# SNC8600.net
KiCad netlist of a schematic drawn in Altium Designer
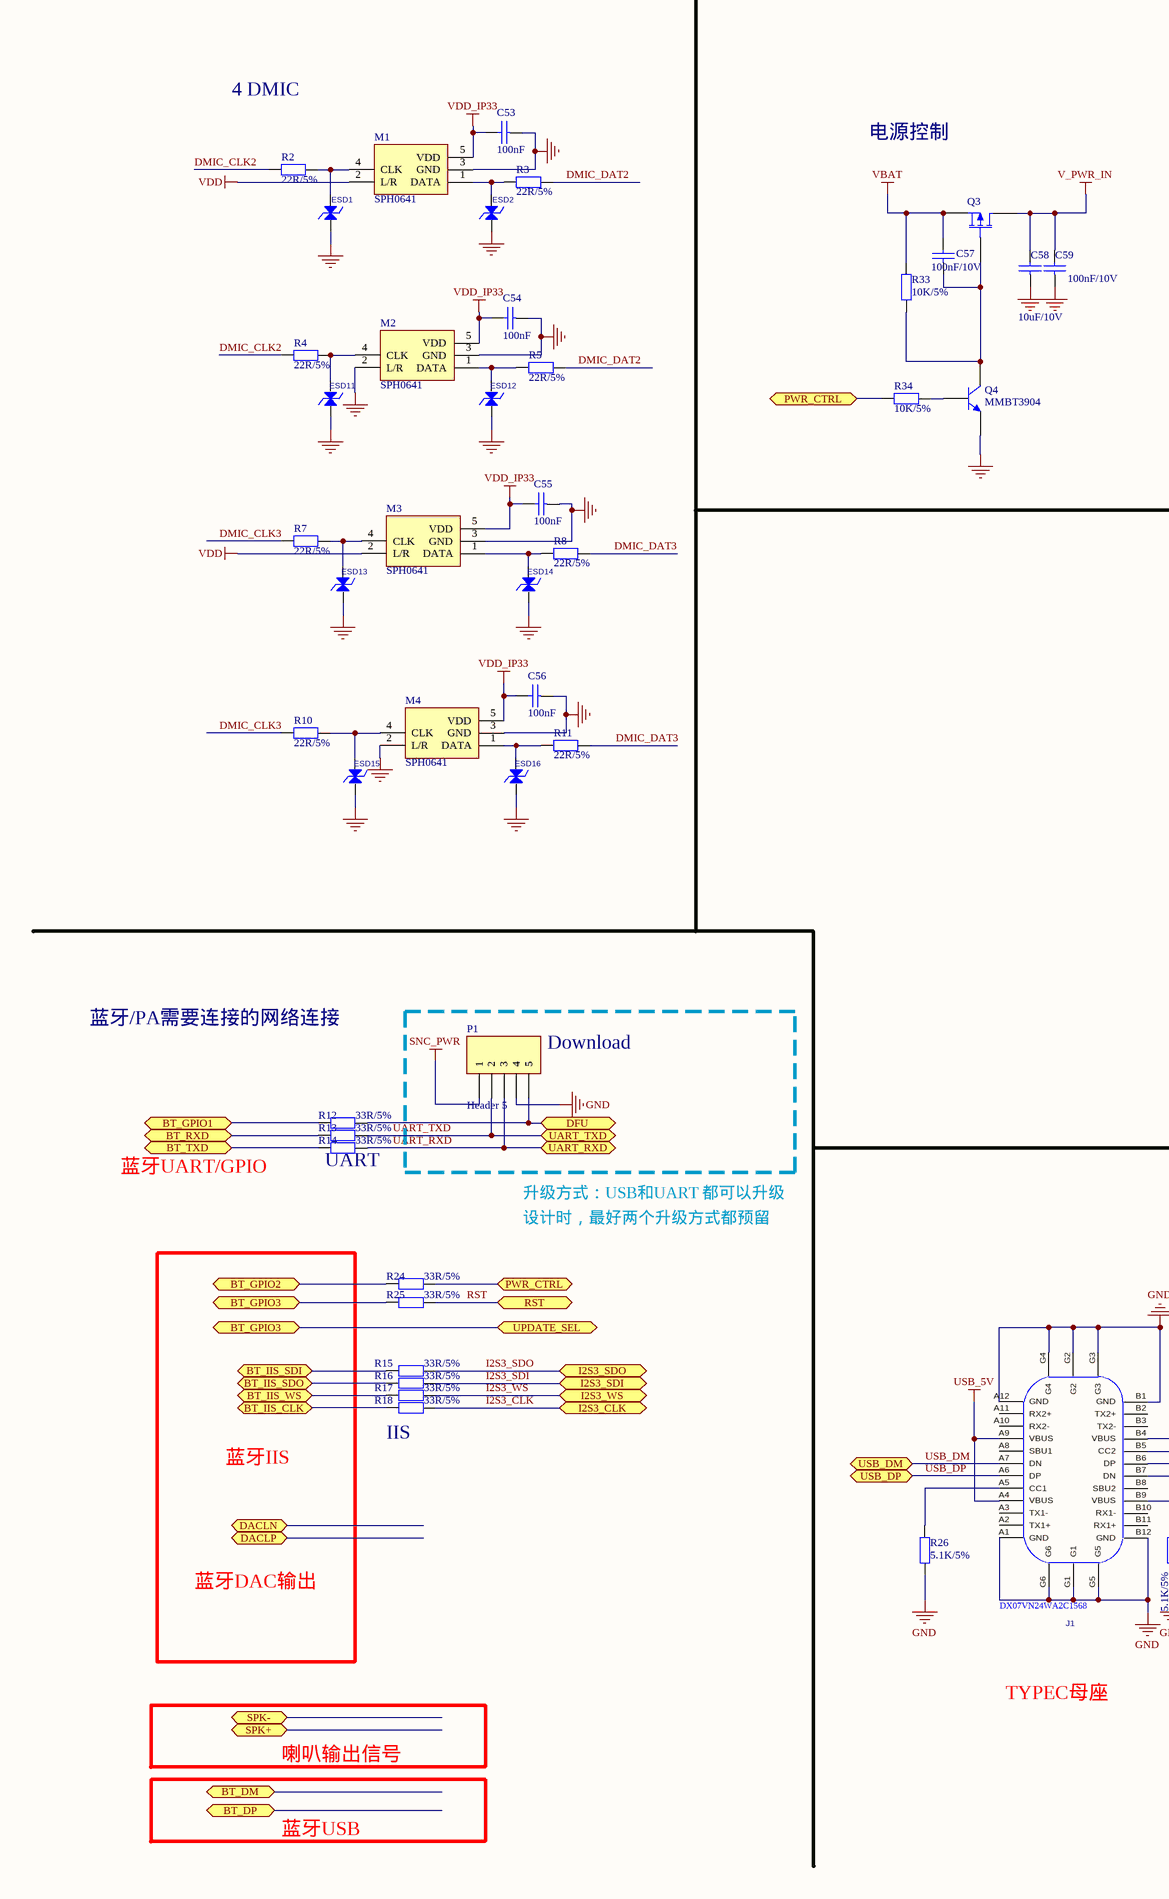
[diagram p0: SNC8600.SchDoc, left]
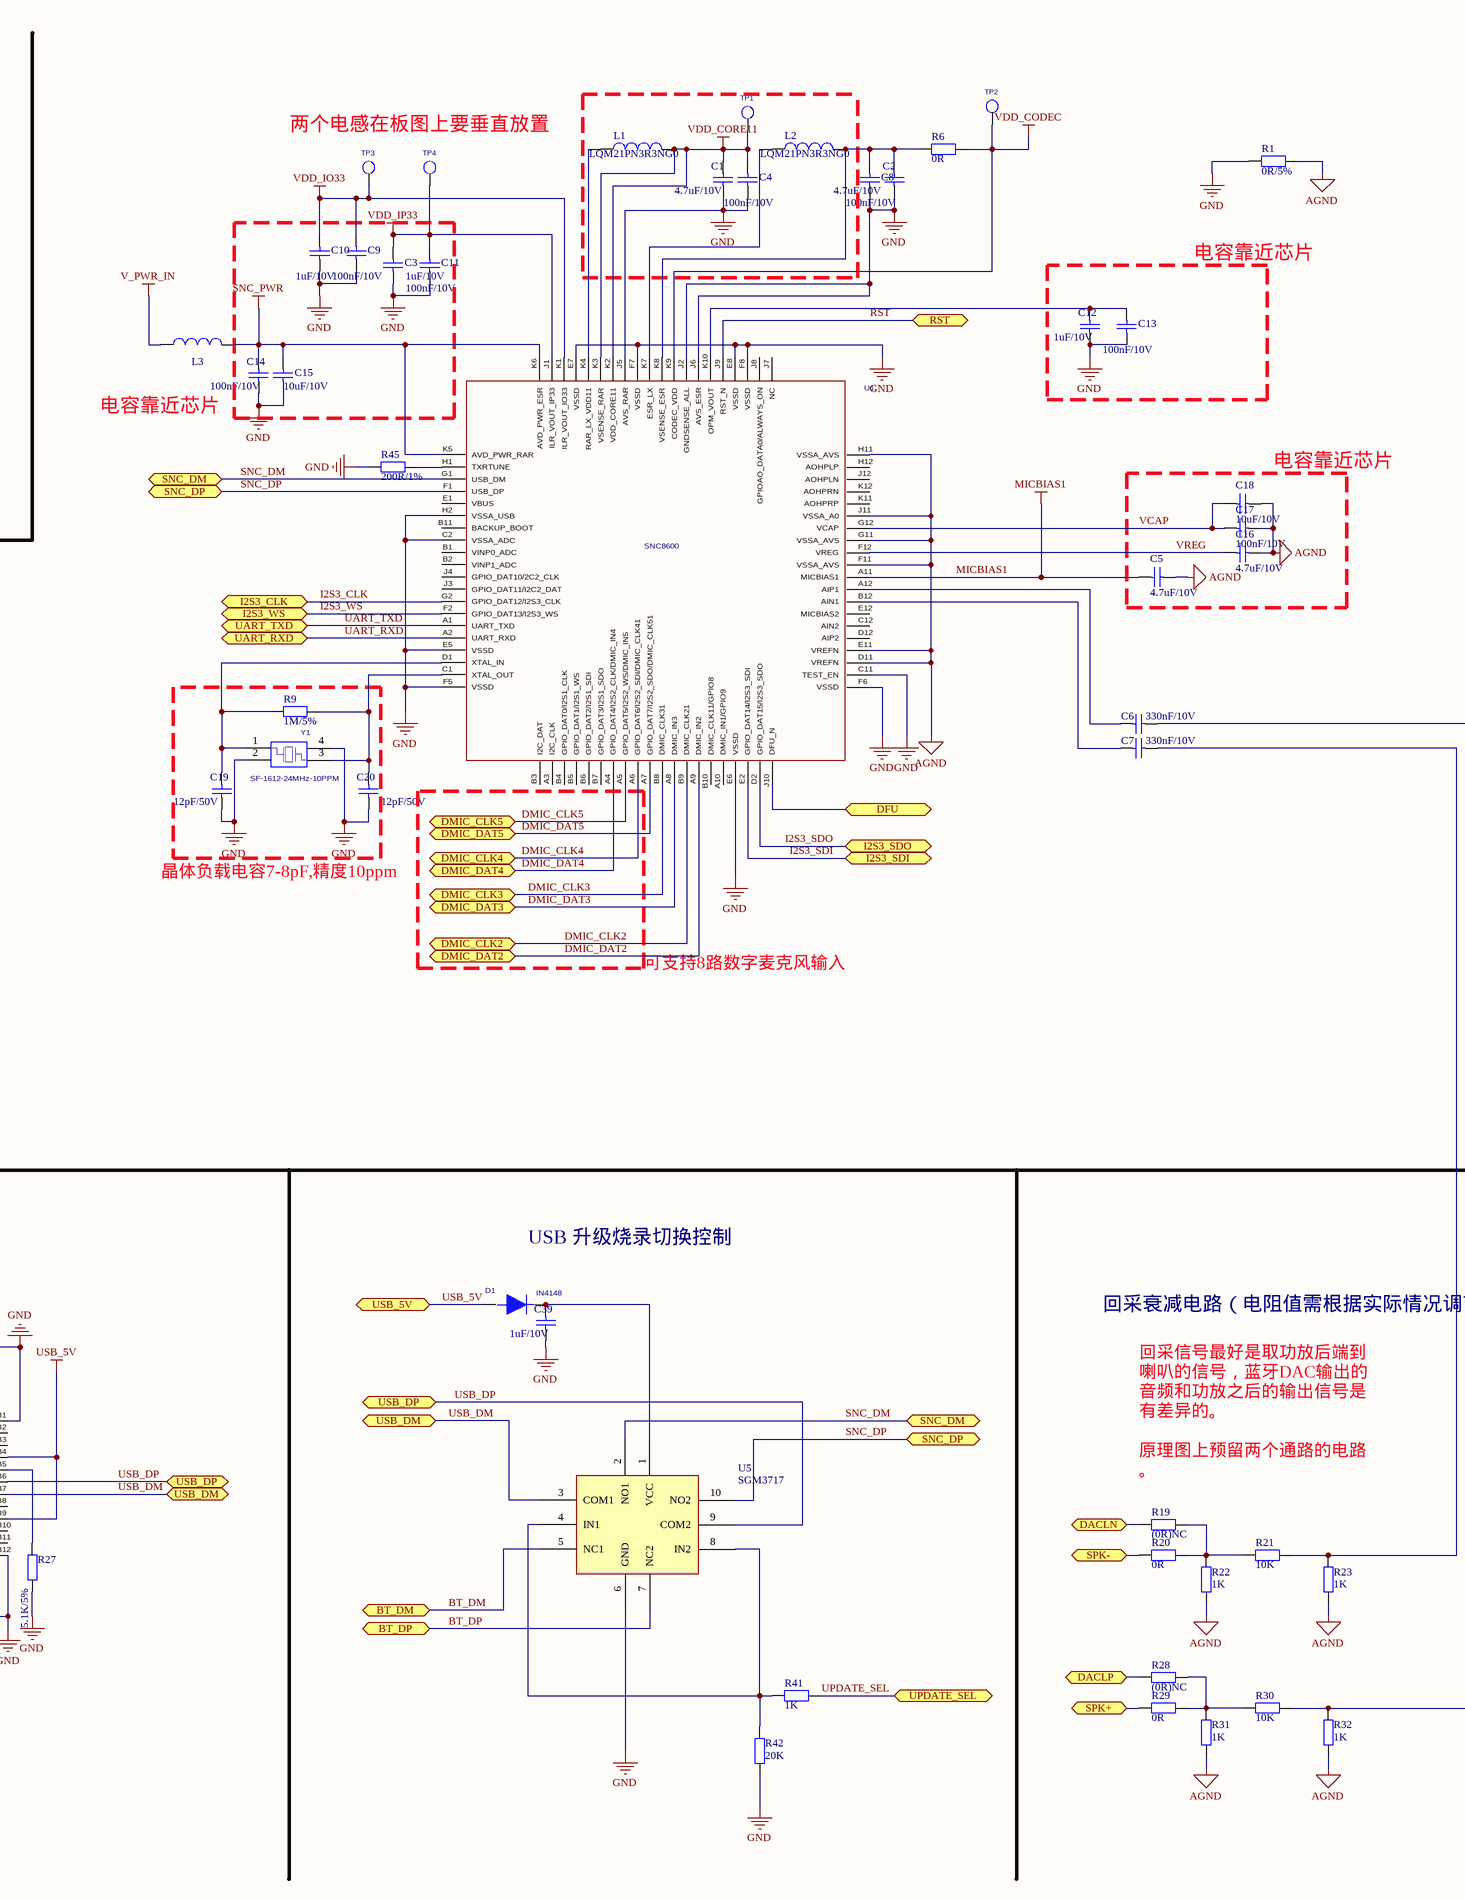
[diagram p1: SNC8600.SchDoc, right]

(export (version "E")
  (design (tool "Eeschema 10.0.6"))
  (components
    (comp (ref "C1")
      (value "4.7uF/10V")
      (footprint "C0603")
      (description "Capacitor (Semiconductor SIM Model)")
      (fields (field (name "PUBLISHER") "Altium Limited"))
      (libsource (lib "Miscellaneous Devices") (part "Cap Semi"))
    )
    (comp (ref "C2")
      (value "4.7uF/10V")
      (footprint "C0603")
      (description "Capacitor (Semiconductor SIM Model)")
      (fields (field (name "PUBLISHER") "Altium Limited"))
      (libsource (lib "Miscellaneous Devices") (part "Cap Semi"))
    )
    (comp (ref "C3")
      (value "1uF/10V")
      (footprint "C0603")
      (description "Capacitor (Semiconductor SIM Model)")
      (fields (field (name "PUBLISHER") "Altium Limited"))
      (libsource (lib "Miscellaneous Devices") (part "Cap Semi"))
    )
    (comp (ref "C4")
      (value "100nF/10V")
      (footprint "C0603")
      (description "Capacitor (Semiconductor SIM Model)")
      (fields (field (name "PUBLISHER") "Altium Limited"))
      (libsource (lib "Miscellaneous Devices") (part "Cap Semi"))
    )
    (comp (ref "C5")
      (value "4.7uF/10V")
      (footprint "C0603")
      (description "Capacitor (Semiconductor SIM Model)")
      (fields (field (name "PUBLISHER") "Altium Limited"))
      (libsource (lib "Miscellaneous Devices") (part "Cap Semi"))
    )
    (comp (ref "C6")
      (value "330nF/10V")
      (footprint "C0603")
      (description "Capacitor (Semiconductor SIM Model)")
      (fields (field (name "PUBLISHER") "Altium Limited"))
      (libsource (lib "Miscellaneous Devices") (part "Cap Semi"))
    )
    (comp (ref "C7")
      (value "330nF/10V")
      (footprint "C0603")
      (description "Capacitor (Semiconductor SIM Model)")
      (fields (field (name "PUBLISHER") "Altium Limited"))
      (libsource (lib "Miscellaneous Devices") (part "Cap Semi"))
    )
    (comp (ref "C8")
      (value "100nF/10V")
      (footprint "C0603")
      (description "Capacitor (Semiconductor SIM Model)")
      (fields (field (name "PUBLISHER") "Altium Limited"))
      (libsource (lib "Miscellaneous Devices") (part "Cap Semi"))
    )
    (comp (ref "C9")
      (value "100nF/10V")
      (footprint "C0603")
      (description "Capacitor (Semiconductor SIM Model)")
      (fields (field (name "PUBLISHER") "Altium Limited"))
      (libsource (lib "Miscellaneous Devices") (part "Cap Semi"))
    )
    (comp (ref "C10")
      (value "1uF/10V")
      (footprint "C0603")
      (description "Capacitor (Semiconductor SIM Model)")
      (fields (field (name "PUBLISHER") "Altium Limited"))
      (libsource (lib "Miscellaneous Devices") (part "Cap Semi"))
    )
    (comp (ref "C11")
      (value "100nF/10V")
      (footprint "C0603")
      (description "Capacitor (Semiconductor SIM Model)")
      (fields (field (name "PUBLISHER") "Altium Limited"))
      (libsource (lib "Miscellaneous Devices") (part "Cap Semi"))
    )
    (comp (ref "C12")
      (value "1uF/10V")
      (footprint "C0603")
      (description "Capacitor (Semiconductor SIM Model)")
      (fields (field (name "PUBLISHER") "Altium Limited"))
      (libsource (lib "Miscellaneous Devices") (part "Cap Semi"))
    )
    (comp (ref "C13")
      (value "100nF/10V")
      (footprint "C0603")
      (description "Capacitor (Semiconductor SIM Model)")
      (fields (field (name "PUBLISHER") "Altium Limited"))
      (libsource (lib "Miscellaneous Devices") (part "Cap Semi"))
    )
    (comp (ref "C14")
      (value "100nF/10V")
      (footprint "C0603")
      (description "Capacitor (Semiconductor SIM Model)")
      (fields (field (name "PUBLISHER") "Altium Limited"))
      (libsource (lib "Miscellaneous Devices") (part "Cap Semi"))
    )
    (comp (ref "C15")
      (value "10uF/10V")
      (footprint "C0603")
      (description "Capacitor (Semiconductor SIM Model)")
      (fields (field (name "PUBLISHER") "Altium Limited"))
      (libsource (lib "Miscellaneous Devices") (part "Cap Semi"))
    )
    (comp (ref "C16")
      (value "4.7uF/10V")
      (footprint "C0603")
      (description "Capacitor (Semiconductor SIM Model)")
      (fields (field (name "PUBLISHER") "Altium Limited"))
      (libsource (lib "Miscellaneous Devices") (part "Cap Semi"))
    )
    (comp (ref "C17")
      (value "100nF/10V")
      (footprint "C0603")
      (description "Capacitor (Semiconductor SIM Model)")
      (fields (field (name "PUBLISHER") "Altium Limited"))
      (libsource (lib "Miscellaneous Devices") (part "Cap Semi"))
    )
    (comp (ref "C18")
      (value "10uF/10V")
      (footprint "C0603")
      (description "Capacitor (Semiconductor SIM Model)")
      (fields (field (name "PUBLISHER") "Altium Limited"))
      (libsource (lib "Miscellaneous Devices") (part "Cap Semi"))
    )
    (comp (ref "C19")
      (value "12pF/50V")
      (footprint "C0603")
      (description "Capacitor (Semiconductor SIM Model)")
      (fields (field (name "PUBLISHER") "Altium Limited"))
      (libsource (lib "Miscellaneous Devices") (part "Cap Semi"))
    )
    (comp (ref "C20")
      (value "12pF/50V")
      (footprint "C0603")
      (description "Capacitor (Semiconductor SIM Model)")
      (fields (field (name "PUBLISHER") "Altium Limited"))
      (libsource (lib "Miscellaneous Devices") (part "Cap Semi"))
    )
    (comp (ref "C39")
      (value "1uF/10V")
      (footprint "C0603")
      (description "Capacitor (Semiconductor SIM Model)")
      (fields (field (name "PUBLISHER") "Altium Limited"))
      (libsource (lib "Miscellaneous Devices") (part "Cap Semi"))
    )
    (comp (ref "C53")
      (value "100nF")
      (footprint "0201")
      (description "Capacitor")
      (libsource (lib "MIC1") (part "CAP-0201"))
    )
    (comp (ref "C54")
      (value "100nF")
      (footprint "0201")
      (description "Capacitor")
      (libsource (lib "MIC1") (part "CAP-0201"))
    )
    (comp (ref "C55")
      (value "100nF")
      (footprint "0201")
      (description "Capacitor")
      (libsource (lib "MIC1") (part "CAP-0201"))
    )
    (comp (ref "C56")
      (value "100nF")
      (footprint "0201")
      (description "Capacitor")
      (libsource (lib "MIC1") (part "CAP-0201"))
    )
    (comp (ref "C57")
      (value "100nF/10V")
      (footprint "0201")
      (description "Capacitor")
      (libsource (lib "*") (part "CAP"))
    )
    (comp (ref "C58")
      (value "10uF/10V")
      (footprint "C0402")
      (description "Capacitor")
      (libsource (lib "电容") (part "普通电容"))
    )
    (comp (ref "C59")
      (value "100nF/10V")
      (footprint "0201")
      (description "Capacitor")
      (libsource (lib "电容") (part "普通电容"))
    )
    (comp (ref "D1")
      (value "IN4148")
      (footprint "SMD")
      (fields (field (name "Comment") "D-IN4148-SMT"))
      (libsource (lib "*") (part "D-IN4148-SMT"))
    )
    (comp (ref "ESD1")
      (value "~")
      (footprint "0402 DFN")
      (libsource (lib "EVB-SCH-LCD-202003152") (part "ESD"))
    )
    (comp (ref "ESD2")
      (value "~")
      (footprint "0402 DFN")
      (libsource (lib "EVB-SCH-LCD-202003152") (part "ESD"))
    )
    (comp (ref "ESD11")
      (value "~")
      (footprint "0402 DFN")
      (libsource (lib "EVB-SCH-LCD-202003152") (part "ESD"))
    )
    (comp (ref "ESD12")
      (value "~")
      (footprint "0402 DFN")
      (libsource (lib "EVB-SCH-LCD-202003152") (part "ESD"))
    )
    (comp (ref "ESD13")
      (value "~")
      (footprint "0402 DFN")
      (libsource (lib "EVB-SCH-LCD-202003152") (part "ESD"))
    )
    (comp (ref "ESD14")
      (value "~")
      (footprint "0402 DFN")
      (libsource (lib "EVB-SCH-LCD-202003152") (part "ESD"))
    )
    (comp (ref "ESD15")
      (value "~")
      (footprint "0402 DFN")
      (libsource (lib "EVB-SCH-LCD-202003152") (part "ESD"))
    )
    (comp (ref "ESD16")
      (value "~")
      (footprint "0402 DFN")
      (libsource (lib "EVB-SCH-LCD-202003152") (part "ESD"))
    )
    (comp (ref "J1")
      (value "TYPEC")
      (footprint "USB-TYPEC")
      (libsource (lib "EVB-SCH-LCD-202003152") (part "TYPEC"))
    )
    (comp (ref "L1")
      (value "LQM21PN3R3NG0")
      (footprint "L0805")
      (description "Inductor")
      (fields (field (name "PUBLISHER") "Altium Limited"))
      (libsource (lib "Miscellaneous Devices") (part "Inductor"))
    )
    (comp (ref "L2")
      (value "LQM21PN3R3NG0")
      (footprint "L0805")
      (description "Inductor")
      (fields (field (name "PUBLISHER") "Altium Limited"))
      (libsource (lib "Miscellaneous Devices") (part "Inductor"))
    )
    (comp (ref "L3")
      (value "~")
      (footprint "R0402")
      (description "Inductor")
      (fields (field (name "PUBLISHER") "Altium Limited"))
      (libsource (lib "Miscellaneous Devices") (part "Inductor"))
    )
    (comp (ref "M1")
      (value "SPH0641")
      (footprint "SPH_3526")
      (description "MEMS MICPHONE")
      (fields (field (name "PUBLISHER") "Altium Limited"))
      (libsource (lib "MIC1") (part "SPH0641"))
    )
    (comp (ref "M2")
      (value "SPH0641")
      (footprint "SPH_3526")
      (description "MEMS MICPHONE")
      (fields (field (name "PUBLISHER") "Altium Limited"))
      (libsource (lib "MIC1") (part "SPH0641"))
    )
    (comp (ref "M3")
      (value "SPH0641")
      (footprint "SPH_3526")
      (description "MEMS MICPHONE")
      (fields (field (name "PUBLISHER") "Altium Limited"))
      (libsource (lib "MIC1") (part "SPH0641"))
    )
    (comp (ref "M4")
      (value "SPH0641")
      (footprint "SPH_3526")
      (description "MEMS MICPHONE")
      (fields (field (name "PUBLISHER") "Altium Limited"))
      (libsource (lib "MIC1") (part "SPH0641"))
    )
    (comp (ref "P1")
      (value "Header 5")
      (footprint "HDR1X5")
      (description "Header, 5-Pin")
      (fields (field (name "PUBLISHER") "Altium Limited"))
      (libsource (lib "Miscellaneous Connectors") (part "Header 5"))
    )
    (comp (ref "Q3")
      (value "~")
      (footprint "SOT23_3407")
      (description "P-Channel MOSFET")
      (fields (field (name "PUBLISHER") "Altium Limited"))
      (libsource (lib "Miscellaneous Devices") (part "MOSFET-P"))
    )
    (comp (ref "Q4")
      (value "MMBT3904")
      (footprint "SOT23")
      (description "NPN General Purpose Amplifier")
      (fields (field (name "PUBLISHER") "Altium Limited"))
      (libsource (lib "Miscellaneous Devices") (part "2N3904"))
    )
    (comp (ref "R1")
      (value "0R/5%")
      (footprint "R0603")
      (description "Resistor")
      (fields (field (name "PUBLISHER") "Altium Limited"))
      (libsource (lib "") (part "Res2_1"))
    )
    (comp (ref "R2")
      (value "22R/5%")
      (footprint "0201")
      (description "Resistor")
      (fields (field (name "PUBLISHER") "Altium Limited"))
      (libsource (lib "Miscellaneous Devices") (part "Res2"))
    )
    (comp (ref "R3")
      (value "22R/5%")
      (footprint "0201")
      (description "Resistor")
      (fields (field (name "PUBLISHER") "Altium Limited"))
      (libsource (lib "Miscellaneous Devices") (part "Res2"))
    )
    (comp (ref "R4")
      (value "22R/5%")
      (footprint "0201")
      (description "Resistor")
      (fields (field (name "PUBLISHER") "Altium Limited"))
      (libsource (lib "Miscellaneous Devices") (part "Res2"))
    )
    (comp (ref "R5")
      (value "22R/5%")
      (footprint "0201")
      (description "Resistor")
      (fields (field (name "PUBLISHER") "Altium Limited"))
      (libsource (lib "Miscellaneous Devices") (part "Res2"))
    )
    (comp (ref "R6")
      (value "0R")
      (footprint "R0603")
      (description "Resistor")
      (fields (field (name "PUBLISHER") "Altium Limited"))
      (libsource (lib "") (part "Res2_1"))
    )
    (comp (ref "R7")
      (value "22R/5%")
      (footprint "0201")
      (description "Resistor")
      (fields (field (name "PUBLISHER") "Altium Limited"))
      (libsource (lib "Miscellaneous Devices") (part "Res2"))
    )
    (comp (ref "R8")
      (value "22R/5%")
      (footprint "0201")
      (description "Resistor")
      (fields (field (name "PUBLISHER") "Altium Limited"))
      (libsource (lib "Miscellaneous Devices") (part "Res2"))
    )
    (comp (ref "R9")
      (value "1M/5%")
      (footprint "R0603")
      (description "Resistor")
      (fields (field (name "PUBLISHER") "Altium Limited"))
      (libsource (lib "") (part "Res2_1"))
    )
    (comp (ref "R10")
      (value "22R/5%")
      (footprint "0201")
      (description "Resistor")
      (fields (field (name "PUBLISHER") "Altium Limited"))
      (libsource (lib "Miscellaneous Devices") (part "Res2"))
    )
    (comp (ref "R11")
      (value "22R/5%")
      (footprint "0201")
      (description "Resistor")
      (fields (field (name "PUBLISHER") "Altium Limited"))
      (libsource (lib "Miscellaneous Devices") (part "Res2"))
    )
    (comp (ref "R12")
      (value "33R/5%")
      (footprint "R0603")
      (description "Resistor")
      (fields (field (name "PUBLISHER") "Altium Limited"))
      (libsource (lib "Miscellaneous Devices") (part "Res2"))
    )
    (comp (ref "R13")
      (value "33R/5%")
      (footprint "R0603")
      (description "Resistor")
      (fields (field (name "PUBLISHER") "Altium Limited"))
      (libsource (lib "Miscellaneous Devices") (part "Res2"))
    )
    (comp (ref "R14")
      (value "33R/5%")
      (footprint "R0603")
      (description "Resistor")
      (fields (field (name "PUBLISHER") "Altium Limited"))
      (libsource (lib "Miscellaneous Devices") (part "Res2"))
    )
    (comp (ref "R15")
      (value "33R/5%")
      (footprint "R0603")
      (description "Resistor")
      (fields (field (name "PUBLISHER") "Altium Limited"))
      (libsource (lib "Miscellaneous Devices") (part "Res2"))
    )
    (comp (ref "R16")
      (value "33R/5%")
      (footprint "R0603")
      (description "Resistor")
      (fields (field (name "PUBLISHER") "Altium Limited"))
      (libsource (lib "Miscellaneous Devices") (part "Res2"))
    )
    (comp (ref "R17")
      (value "33R/5%")
      (footprint "R0603")
      (description "Resistor")
      (fields (field (name "PUBLISHER") "Altium Limited"))
      (libsource (lib "Miscellaneous Devices") (part "Res2"))
    )
    (comp (ref "R18")
      (value "33R/5%")
      (footprint "R0603")
      (description "Resistor")
      (fields (field (name "PUBLISHER") "Altium Limited"))
      (libsource (lib "Miscellaneous Devices") (part "Res2"))
    )
    (comp (ref "R19")
      (value "(0R)NC")
      (footprint "R0603")
      (description "Resistor")
      (fields (field (name "PUBLISHER") "Altium Limited"))
      (libsource (lib "") (part "Res2_1"))
    )
    (comp (ref "R20")
      (value "0R")
      (footprint "R0603")
      (description "Resistor")
      (fields (field (name "PUBLISHER") "Altium Limited"))
      (libsource (lib "") (part "Res2_1"))
    )
    (comp (ref "R21")
      (value "10K")
      (footprint "R0603")
      (description "Resistor")
      (fields (field (name "PUBLISHER") "Altium Limited"))
      (libsource (lib "") (part "Res2_1"))
    )
    (comp (ref "R22")
      (value "1K")
      (footprint "R0603")
      (description "Resistor")
      (fields (field (name "PUBLISHER") "Altium Limited"))
      (libsource (lib "") (part "Res2_2"))
    )
    (comp (ref "R23")
      (value "1K")
      (footprint "R0603")
      (description "Resistor")
      (fields (field (name "PUBLISHER") "Altium Limited"))
      (libsource (lib "") (part "Res2_2"))
    )
    (comp (ref "R24")
      (value "33R/5%")
      (footprint "R0603")
      (description "Resistor")
      (fields (field (name "PUBLISHER") "Altium Limited"))
      (libsource (lib "Miscellaneous Devices") (part "Res2"))
    )
    (comp (ref "R25")
      (value "33R/5%")
      (footprint "R0603")
      (description "Resistor")
      (fields (field (name "PUBLISHER") "Altium Limited"))
      (libsource (lib "Miscellaneous Devices") (part "Res2"))
    )
    (comp (ref "R26")
      (value "5.1K/5%")
      (footprint "R0603")
      (description "Resistor")
      (fields (field (name "PUBLISHER") "Altium Limited"))
      (libsource (lib "") (part "Res2_2"))
    )
    (comp (ref "R27")
      (value "5.1K/5%")
      (footprint "R0603")
      (description "Resistor")
      (fields (field (name "PUBLISHER") "Altium Limited"))
      (libsource (lib "") (part "Res2_2"))
    )
    (comp (ref "R28")
      (value "(0R)NC")
      (footprint "R0603")
      (description "Resistor")
      (fields (field (name "PUBLISHER") "Altium Limited"))
      (libsource (lib "") (part "Res2_1"))
    )
    (comp (ref "R29")
      (value "0R")
      (footprint "R0603")
      (description "Resistor")
      (fields (field (name "PUBLISHER") "Altium Limited"))
      (libsource (lib "") (part "Res2_1"))
    )
    (comp (ref "R30")
      (value "10K")
      (footprint "R0603")
      (description "Resistor")
      (fields (field (name "PUBLISHER") "Altium Limited"))
      (libsource (lib "") (part "Res2_1"))
    )
    (comp (ref "R31")
      (value "1K")
      (footprint "R0603")
      (description "Resistor")
      (fields (field (name "PUBLISHER") "Altium Limited"))
      (libsource (lib "") (part "Res2_2"))
    )
    (comp (ref "R32")
      (value "1K")
      (footprint "R0603")
      (description "Resistor")
      (fields (field (name "PUBLISHER") "Altium Limited"))
      (libsource (lib "") (part "Res2_2"))
    )
    (comp (ref "R33")
      (value "10K/5%")
      (footprint "0201")
      (description "Resistor")
      (fields (field (name "PUBLISHER") "Altium Limited"))
      (libsource (lib "") (part "Res2_2"))
    )
    (comp (ref "R34")
      (value "10K/5%")
      (footprint "0201")
      (description "Resistor")
      (fields (field (name "PUBLISHER") "Altium Limited"))
      (libsource (lib "Miscellaneous Devices") (part "Res2"))
    )
    (comp (ref "R41")
      (value "1K")
      (footprint "R0603")
      (description "Resistor")
      (fields (field (name "PUBLISHER") "Altium Limited"))
      (libsource (lib "") (part "Res2_1"))
    )
    (comp (ref "R42")
      (value "20K")
      (footprint "R0603")
      (description "Resistor")
      (fields (field (name "PUBLISHER") "Altium Limited"))
      (libsource (lib "") (part "Res2_2"))
    )
    (comp (ref "R45")
      (value "200R/1%")
      (footprint "R0603")
      (description "Resistor")
      (fields (field (name "PUBLISHER") "Altium Limited"))
      (libsource (lib "Miscellaneous Devices") (part "Res2"))
    )
    (comp (ref "TP1")
      (value "TP1")
      (footprint "TP1-1MM")
      (libsource (lib "EVB-SCH-LCD-202003152") (part "TP1"))
    )
    (comp (ref "TP2")
      (value "TP1")
      (footprint "TP1-1MM")
      (libsource (lib "EVB-SCH-LCD-202003152") (part "TP1"))
    )
    (comp (ref "TP3")
      (value "TP1")
      (footprint "TP1-1MM")
      (libsource (lib "EVB-SCH-LCD-202003152") (part "TP1"))
    )
    (comp (ref "TP4")
      (value "TP1")
      (footprint "TP1-1MM")
      (libsource (lib "EVB-SCH-LCD-202003152") (part "TP1"))
    )
    (comp (ref "U1")
      (value "SNC8600")
      (footprint "BGA0405-2")
      (libsource (lib "EVB-SCH-LCD-202003152") (part "BGA_BCHIP-ES2"))
    )
    (comp (ref "U5")
      (value "SGM3717")
      (footprint "UQFN10")
      (libsource (lib "EVB-SCH-LCD-202003152") (part "NLAS2750"))
    )
    (comp (ref "Y1")
      (value "SF-1612-24MHz-10PPM")
      (footprint "SF1612")
      (fields (field (name "Comment") "SF1612"))
      (libsource (lib "EVB-SCH-LCD-202003152") (part "SF1612"))
    )
  )
  (nets
    (net (code "1") (name "/BT_DM") (class "Default")
      (node (ref "U5") (pin "5") (pinfunction "NC1_5") (pintype "passive"))
    )
    (net (code "2") (name "/BT_DP") (class "Default")
      (node (ref "U5") (pin "7") (pinfunction "NC2_7") (pintype "passive"))
    )
    (net (code "3") (name "/BT_GPIO1") (class "Default")
      (node (ref "R12") (pin "1") (pinfunction "1_1") (pintype "passive"))
    )
    (net (code "4") (name "/BT_GPIO2") (class "Default")
      (node (ref "R24") (pin "1") (pinfunction "1_1") (pintype "passive"))
    )
    (net (code "5") (name "/BT_IIS_CLK") (class "Default")
      (node (ref "R18") (pin "1") (pinfunction "1_1") (pintype "passive"))
    )
    (net (code "6") (name "/BT_IIS_SDI") (class "Default")
      (node (ref "R15") (pin "1") (pinfunction "1_1") (pintype "passive"))
    )
    (net (code "7") (name "/BT_IIS_SDO") (class "Default")
      (node (ref "R16") (pin "1") (pinfunction "1_1") (pintype "passive"))
    )
    (net (code "8") (name "/BT_IIS_WS") (class "Default")
      (node (ref "R17") (pin "1") (pinfunction "1_1") (pintype "passive"))
    )
    (net (code "9") (name "/BT_RXD") (class "Default")
      (node (ref "R13") (pin "1") (pinfunction "1_1") (pintype "passive"))
    )
    (net (code "10") (name "/BT_TXD") (class "Default")
      (node (ref "R14") (pin "1") (pinfunction "1_1") (pintype "passive"))
    )
    (net (code "11") (name "/DACLN") (class "Default")
      (node (ref "R19") (pin "2") (pinfunction "2_2") (pintype "passive"))
    )
    (net (code "12") (name "/DACLP") (class "Default")
      (node (ref "R28") (pin "2") (pinfunction "2_2") (pintype "passive"))
    )
    (net (code "13") (name "/DFU") (class "Default")
      (node (ref "P1") (pin "5") (pinfunction "5_5") (pintype "passive"))
      (node (ref "R12") (pin "2") (pinfunction "2_2") (pintype "passive"))
      (node (ref "U1") (pin "J10") (pinfunction "DFU_N_J10") (pintype "passive"))
    )
    (net (code "14") (name "/DMIC_CLK2") (class "Default")
      (node (ref "R2") (pin "1") (pinfunction "1_1") (pintype "passive"))
      (node (ref "R4") (pin "1") (pinfunction "1_1") (pintype "passive"))
      (node (ref "U1") (pin "B9") (pinfunction "DMIC_CLK21_B9") (pintype "passive"))
    )
    (net (code "15") (name "/DMIC_CLK3") (class "Default")
      (node (ref "R10") (pin "1") (pinfunction "1_1") (pintype "passive"))
      (node (ref "R7") (pin "1") (pinfunction "1_1") (pintype "passive"))
      (node (ref "U1") (pin "B8") (pinfunction "DMIC_CLK31_B8") (pintype "passive"))
    )
    (net (code "16") (name "/DMIC_CLK4") (class "Default")
      (node (ref "U1") (pin "A6") (pinfunction "GPIO_DAT6/I2S2_SDI/DMIC_CLK41_A6") (pintype "passive"))
    )
    (net (code "17") (name "/DMIC_CLK5") (class "Default")
      (node (ref "U1") (pin "A5") (pinfunction "GPIO_DAT5/I2S2_WS/DMIC_IN5_A5") (pintype "passive"))
    )
    (net (code "18") (name "/DMIC_DAT2") (class "Default")
      (node (ref "R3") (pin "2") (pinfunction "2_2") (pintype "passive"))
      (node (ref "R5") (pin "2") (pinfunction "2_2") (pintype "passive"))
      (node (ref "U1") (pin "A9") (pinfunction "DMIC_IN2_A9") (pintype "passive"))
    )
    (net (code "19") (name "/DMIC_DAT3") (class "Default")
      (node (ref "R11") (pin "2") (pinfunction "2_2") (pintype "passive"))
      (node (ref "R8") (pin "2") (pinfunction "2_2") (pintype "passive"))
      (node (ref "U1") (pin "A8") (pinfunction "DMIC_IN3_A8") (pintype "passive"))
    )
    (net (code "20") (name "/DMIC_DAT4") (class "Default")
      (node (ref "U1") (pin "A4") (pinfunction "GPIO_DAT4/I2S2_CLK/DMIC_IN4_A4") (pintype "passive"))
    )
    (net (code "21") (name "/DMIC_DAT5") (class "Default")
      (node (ref "U1") (pin "A7") (pinfunction "GPIO_DAT7/I2S2_SDO/DMIC_CLK51_A7") (pintype "passive"))
    )
    (net (code "22") (name "/I2S3_CLK") (class "Default")
      (node (ref "R18") (pin "2") (pinfunction "2_2") (pintype "passive"))
      (node (ref "U1") (pin "G2") (pinfunction "GPIO_DAT12/I2S3_CLK_G2") (pintype "passive"))
    )
    (net (code "23") (name "/I2S3_SDI") (class "Default")
      (node (ref "R16") (pin "2") (pinfunction "2_2") (pintype "passive"))
      (node (ref "U1") (pin "E2") (pinfunction "GPIO_DAT14/I2S3_SDI_E2") (pintype "passive"))
    )
    (net (code "24") (name "/I2S3_SDO") (class "Default")
      (node (ref "R15") (pin "2") (pinfunction "2_2") (pintype "passive"))
      (node (ref "U1") (pin "D2") (pinfunction "GPIO_DAT15/I2S3_SDO_D2") (pintype "passive"))
    )
    (net (code "25") (name "/I2S3_WS") (class "Default")
      (node (ref "R17") (pin "2") (pinfunction "2_2") (pintype "passive"))
      (node (ref "U1") (pin "F2") (pinfunction "GPIO_DAT13/I2S3_WS_F2") (pintype "passive"))
    )
    (net (code "26") (name "/PWR_CTRL") (class "Default")
      (node (ref "R24") (pin "2") (pinfunction "2_2") (pintype "passive"))
      (node (ref "R34") (pin "1") (pinfunction "1_1") (pintype "passive"))
    )
    (net (code "27") (name "/RST") (class "Default")
      (node (ref "R25") (pin "2") (pinfunction "2_2") (pintype "passive"))
      (node (ref "U1") (pin "J9") (pinfunction "RST_N_J9") (pintype "passive"))
    )
    (net (code "28") (name "/SNC_DM") (class "Default")
      (node (ref "U1") (pin "G1") (pinfunction "USB_DM_G1") (pintype "passive"))
      (node (ref "U5") (pin "2") (pinfunction "NO1_2") (pintype "passive"))
    )
    (net (code "29") (name "/SNC_DP") (class "Default")
      (node (ref "U1") (pin "F1") (pinfunction "USB_DP_F1") (pintype "passive"))
      (node (ref "U5") (pin "10") (pinfunction "NO2_10") (pintype "passive"))
    )
    (net (code "30") (name "/SPK+") (class "Default")
      (node (ref "R29") (pin "2") (pinfunction "2_2") (pintype "passive"))
    )
    (net (code "31") (name "/SPK-") (class "Default")
      (node (ref "R20") (pin "2") (pinfunction "2_2") (pintype "passive"))
    )
    (net (code "32") (name "/UART_RXD") (class "Default")
      (node (ref "P1") (pin "3") (pinfunction "3_3") (pintype "passive"))
      (node (ref "R14") (pin "2") (pinfunction "2_2") (pintype "passive"))
      (node (ref "U1") (pin "A2") (pinfunction "UART_RXD_A2") (pintype "passive"))
    )
    (net (code "33") (name "/UART_TXD") (class "Default")
      (node (ref "P1") (pin "2") (pinfunction "2_2") (pintype "passive"))
      (node (ref "R13") (pin "2") (pinfunction "2_2") (pintype "passive"))
      (node (ref "U1") (pin "A1") (pinfunction "UART_TXD_A1") (pintype "passive"))
    )
    (net (code "34") (name "/UPDATE_SEL") (class "Default")
      (node (ref "R25") (pin "1") (pinfunction "1_1") (pintype "passive"))
      (node (ref "R41") (pin "1") (pinfunction "1_1") (pintype "passive"))
    )
    (net (code "35") (name "/USB_DM") (class "Default")
      (node (ref "J1") (pin "A7") (pinfunction "DN_A7") (pintype "passive"))
      (node (ref "J1") (pin "B7") (pinfunction "DN_B7") (pintype "passive"))
      (node (ref "U5") (pin "3") (pinfunction "COM1_3") (pintype "passive"))
    )
    (net (code "36") (name "/USB_DP") (class "Default")
      (node (ref "J1") (pin "A6") (pinfunction "DP_A6") (pintype "passive"))
      (node (ref "J1") (pin "B6") (pinfunction "DP_B6") (pintype "passive"))
      (node (ref "U5") (pin "9") (pinfunction "COM2_9") (pintype "passive"))
    )
    (net (code "37") (name "/VCAP") (class "Default")
      (node (ref "C17") (pin "2") (pinfunction "2_2") (pintype "passive"))
      (node (ref "C18") (pin "2") (pinfunction "2_2") (pintype "passive"))
      (node (ref "U1") (pin "G12") (pinfunction "VCAP_G12") (pintype "passive"))
    )
    (net (code "38") (name "/VREG") (class "Default")
      (node (ref "C16") (pin "2") (pinfunction "2_2") (pintype "passive"))
      (node (ref "U1") (pin "F12") (pinfunction "VREG_F12") (pintype "passive"))
    )
    (net (code "39") (name "AGND") (class "Default")
      (node (ref "C16") (pin "1") (pinfunction "1_1") (pintype "passive"))
      (node (ref "C17") (pin "1") (pinfunction "1_1") (pintype "passive"))
      (node (ref "C18") (pin "1") (pinfunction "1_1") (pintype "passive"))
      (node (ref "C5") (pin "1") (pinfunction "1_1") (pintype "passive"))
      (node (ref "R1") (pin "1") (pinfunction "1_1") (pintype "passive"))
      (node (ref "R22") (pin "2") (pinfunction "2_2") (pintype "passive"))
      (node (ref "R23") (pin "2") (pinfunction "2_2") (pintype "passive"))
      (node (ref "R31") (pin "2") (pinfunction "2_2") (pintype "passive"))
      (node (ref "R32") (pin "2") (pinfunction "2_2") (pintype "passive"))
      (node (ref "U1") (pin "D11") (pinfunction "VREFN_D11") (pintype "passive"))
      (node (ref "U1") (pin "E11") (pinfunction "VREFN_E11") (pintype "passive"))
      (node (ref "U1") (pin "F11") (pinfunction "VSSA_AVS_F11") (pintype "passive"))
      (node (ref "U1") (pin "G11") (pinfunction "VSSA_AVS_G11") (pintype "passive"))
      (node (ref "U1") (pin "H11") (pinfunction "VSSA_AVS_H11") (pintype "passive"))
      (node (ref "U1") (pin "J11") (pinfunction "VSSA_A0_J11") (pintype "passive"))
    )
    (net (code "40") (name "GND") (class "Default")
      (node (ref "C1") (pin "1") (pinfunction "1_1") (pintype "passive"))
      (node (ref "C10") (pin "1") (pinfunction "1_1") (pintype "passive"))
      (node (ref "C11") (pin "1") (pinfunction "1_1") (pintype "passive"))
      (node (ref "C12") (pin "1") (pinfunction "1_1") (pintype "passive"))
      (node (ref "C13") (pin "1") (pinfunction "1_1") (pintype "passive"))
      (node (ref "C14") (pin "1") (pinfunction "1_1") (pintype "passive"))
      (node (ref "C15") (pin "1") (pinfunction "1_1") (pintype "passive"))
      (node (ref "C19") (pin "1") (pinfunction "1_1") (pintype "passive"))
      (node (ref "C2") (pin "1") (pinfunction "1_1") (pintype "passive"))
      (node (ref "C20") (pin "1") (pinfunction "1_1") (pintype "passive"))
      (node (ref "C3") (pin "1") (pinfunction "1_1") (pintype "passive"))
      (node (ref "C39") (pin "1") (pinfunction "1_1") (pintype "passive"))
      (node (ref "C4") (pin "1") (pinfunction "1_1") (pintype "passive"))
      (node (ref "C53") (pin "1") (pinfunction "1_1") (pintype "passive"))
      (node (ref "C54") (pin "1") (pinfunction "1_1") (pintype "passive"))
      (node (ref "C55") (pin "1") (pinfunction "1_1") (pintype "passive"))
      (node (ref "C56") (pin "1") (pinfunction "1_1") (pintype "passive"))
      (node (ref "C58") (pin "1") (pinfunction "1_1") (pintype "passive"))
      (node (ref "C59") (pin "1") (pinfunction "1_1") (pintype "passive"))
      (node (ref "C8") (pin "1") (pinfunction "1_1") (pintype "passive"))
      (node (ref "C9") (pin "1") (pinfunction "1_1") (pintype "passive"))
      (node (ref "ESD1") (pin "2") (pinfunction "2_2") (pintype "passive"))
      (node (ref "ESD11") (pin "2") (pinfunction "2_2") (pintype "passive"))
      (node (ref "ESD12") (pin "2") (pinfunction "2_2") (pintype "passive"))
      (node (ref "ESD13") (pin "2") (pinfunction "2_2") (pintype "passive"))
      (node (ref "ESD14") (pin "2") (pinfunction "2_2") (pintype "passive"))
      (node (ref "ESD15") (pin "2") (pinfunction "2_2") (pintype "passive"))
      (node (ref "ESD16") (pin "2") (pinfunction "2_2") (pintype "passive"))
      (node (ref "ESD2") (pin "2") (pinfunction "2_2") (pintype "passive"))
      (node (ref "J1") (pin "A1") (pinfunction "GND_A1") (pintype "passive"))
      (node (ref "J1") (pin "A12") (pinfunction "GND_A12") (pintype "passive"))
      (node (ref "J1") (pin "B1") (pinfunction "GND_B1") (pintype "passive"))
      (node (ref "J1") (pin "B12") (pinfunction "GND_B12") (pintype "passive"))
      (node (ref "J1") (pin "G1") (pinfunction "G1_G1") (pintype "passive"))
      (node (ref "J1") (pin "G2") (pinfunction "G2_G2") (pintype "passive"))
      (node (ref "J1") (pin "G3") (pinfunction "G3_G3") (pintype "passive"))
      (node (ref "J1") (pin "G4") (pinfunction "G4_G4") (pintype "passive"))
      (node (ref "J1") (pin "G5") (pinfunction "G5_G5") (pintype "passive"))
      (node (ref "J1") (pin "G6") (pinfunction "G6_G6") (pintype "passive"))
      (node (ref "M1") (pin "3") (pinfunction "GND_3") (pintype "power_in"))
      (node (ref "M2") (pin "2") (pinfunction "L/R_2") (pintype "passive"))
      (node (ref "M2") (pin "3") (pinfunction "GND_3") (pintype "power_in"))
      (node (ref "M3") (pin "3") (pinfunction "GND_3") (pintype "power_in"))
      (node (ref "M4") (pin "2") (pinfunction "L/R_2") (pintype "passive"))
      (node (ref "M4") (pin "3") (pinfunction "GND_3") (pintype "power_in"))
      (node (ref "P1") (pin "4") (pinfunction "4_4") (pintype "passive"))
      (node (ref "Q4") (pin "2") (pinfunction "E_2") (pintype "passive"))
      (node (ref "R1") (pin "2") (pinfunction "2_2") (pintype "passive"))
      (node (ref "R26") (pin "2") (pinfunction "2_2") (pintype "passive"))
      (node (ref "R27") (pin "2") (pinfunction "2_2") (pintype "passive"))
      (node (ref "R42") (pin "2") (pinfunction "2_2") (pintype "passive"))
      (node (ref "R45") (pin "1") (pinfunction "1_1") (pintype "passive"))
      (node (ref "U1") (pin "C11") (pinfunction "TEST_EN_C11") (pintype "passive"))
      (node (ref "U1") (pin "C2") (pinfunction "VSSA_ADC_C2") (pintype "passive"))
      (node (ref "U1") (pin "E5") (pinfunction "VSSD_E5") (pintype "passive"))
      (node (ref "U1") (pin "E6") (pinfunction "VSSD_E6") (pintype "passive"))
      (node (ref "U1") (pin "E7") (pinfunction "VSSD_E7") (pintype "passive"))
      (node (ref "U1") (pin "E8") (pinfunction "VSSD_E8") (pintype "passive"))
      (node (ref "U1") (pin "F5") (pinfunction "VSSD_F5") (pintype "passive"))
      (node (ref "U1") (pin "F6") (pinfunction "VSSD_F6") (pintype "passive"))
      (node (ref "U1") (pin "F7") (pinfunction "VSSD_F7") (pintype "passive"))
      (node (ref "U1") (pin "F8") (pinfunction "VSSD_F8") (pintype "passive"))
      (node (ref "U1") (pin "H2") (pinfunction "VSSA_USB_H2") (pintype "passive"))
      (node (ref "U1") (pin "J2") (pinfunction "GNDSENSE_ALL_J2") (pintype "passive"))
      (node (ref "U1") (pin "J5") (pinfunction "AVS_RAR_J5") (pintype "passive"))
      (node (ref "U1") (pin "J6") (pinfunction "AVS_ESR_J6") (pintype "passive"))
      (node (ref "U5") (pin "6") (pinfunction "GND_6") (pintype "passive"))
      (node (ref "Y1") (pin "2") (pinfunction "2_2") (pintype "passive"))
      (node (ref "Y1") (pin "4") (pinfunction "4_4") (pintype "passive"))
    )
    (net (code "41") (name "MICBIAS1") (class "Default")
      (node (ref "C5") (pin "2") (pinfunction "2_2") (pintype "passive"))
      (node (ref "U1") (pin "A11") (pinfunction "MICBIAS1_A11") (pintype "passive"))
    )
    (net (code "42") (name "Net-(C6-Pad1)") (class "Default")
      (node (ref "C6") (pin "1") (pinfunction "1_1") (pintype "passive"))
      (node (ref "R30") (pin "1") (pinfunction "1_1") (pintype "passive"))
      (node (ref "R32") (pin "1") (pinfunction "1_1") (pintype "passive"))
    )
    (net (code "43") (name "Net-(C7-Pad1)") (class "Default")
      (node (ref "C7") (pin "1") (pinfunction "1_1") (pintype "passive"))
      (node (ref "R21") (pin "1") (pinfunction "1_1") (pintype "passive"))
      (node (ref "R23") (pin "1") (pinfunction "1_1") (pintype "passive"))
    )
    (net (code "44") (name "Net-(J1-CC1)") (class "Default")
      (node (ref "J1") (pin "A5") (pinfunction "CC1_A5") (pintype "passive"))
      (node (ref "R26") (pin "1") (pinfunction "1_1") (pintype "passive"))
    )
    (net (code "45") (name "Net-(J1-CC2)") (class "Default")
      (node (ref "J1") (pin "B5") (pinfunction "CC2_B5") (pintype "passive"))
      (node (ref "R27") (pin "1") (pinfunction "1_1") (pintype "passive"))
    )
    (net (code "46") (name "Net-(M1-CLK)") (class "Default")
      (node (ref "ESD1") (pin "1") (pinfunction "1_1") (pintype "passive"))
      (node (ref "M1") (pin "4") (pinfunction "CLK_4") (pintype "power_in"))
      (node (ref "R2") (pin "2") (pinfunction "2_2") (pintype "passive"))
    )
    (net (code "47") (name "Net-(M1-DATA)") (class "Default")
      (node (ref "ESD2") (pin "1") (pinfunction "1_1") (pintype "passive"))
      (node (ref "M1") (pin "1") (pinfunction "DATA_1") (pintype "passive"))
      (node (ref "R3") (pin "1") (pinfunction "1_1") (pintype "passive"))
    )
    (net (code "48") (name "Net-(M2-CLK)") (class "Default")
      (node (ref "ESD11") (pin "1") (pinfunction "1_1") (pintype "passive"))
      (node (ref "M2") (pin "4") (pinfunction "CLK_4") (pintype "power_in"))
      (node (ref "R4") (pin "2") (pinfunction "2_2") (pintype "passive"))
    )
    (net (code "49") (name "Net-(M2-DATA)") (class "Default")
      (node (ref "ESD12") (pin "1") (pinfunction "1_1") (pintype "passive"))
      (node (ref "M2") (pin "1") (pinfunction "DATA_1") (pintype "passive"))
      (node (ref "R5") (pin "1") (pinfunction "1_1") (pintype "passive"))
    )
    (net (code "50") (name "Net-(M3-CLK)") (class "Default")
      (node (ref "ESD13") (pin "1") (pinfunction "1_1") (pintype "passive"))
      (node (ref "M3") (pin "4") (pinfunction "CLK_4") (pintype "power_in"))
      (node (ref "R7") (pin "2") (pinfunction "2_2") (pintype "passive"))
    )
    (net (code "51") (name "Net-(M3-DATA)") (class "Default")
      (node (ref "ESD14") (pin "1") (pinfunction "1_1") (pintype "passive"))
      (node (ref "M3") (pin "1") (pinfunction "DATA_1") (pintype "passive"))
      (node (ref "R8") (pin "1") (pinfunction "1_1") (pintype "passive"))
    )
    (net (code "52") (name "Net-(M4-CLK)") (class "Default")
      (node (ref "ESD15") (pin "1") (pinfunction "1_1") (pintype "passive"))
      (node (ref "M4") (pin "4") (pinfunction "CLK_4") (pintype "power_in"))
      (node (ref "R10") (pin "2") (pinfunction "2_2") (pintype "passive"))
    )
    (net (code "53") (name "Net-(M4-DATA)") (class "Default")
      (node (ref "ESD16") (pin "1") (pinfunction "1_1") (pintype "passive"))
      (node (ref "M4") (pin "1") (pinfunction "DATA_1") (pintype "passive"))
      (node (ref "R11") (pin "1") (pinfunction "1_1") (pintype "passive"))
    )
    (net (code "54") (name "Net-(Q3-G)") (class "Default")
      (node (ref "C57") (pin "1") (pinfunction "1_1") (pintype "passive"))
      (node (ref "Q3") (pin "2") (pinfunction "G_2") (pintype "passive"))
      (node (ref "Q4") (pin "3") (pinfunction "C_3") (pintype "passive"))
      (node (ref "R33") (pin "2") (pinfunction "2_2") (pintype "passive"))
    )
    (net (code "55") (name "Net-(Q4-B)") (class "Default")
      (node (ref "Q4") (pin "1") (pinfunction "B_1") (pintype "passive"))
      (node (ref "R34") (pin "2") (pinfunction "2_2") (pintype "passive"))
    )
    (net (code "56") (name "Net-(R19-Pad1)") (class "Default")
      (node (ref "R19") (pin "1") (pinfunction "1_1") (pintype "passive"))
      (node (ref "R20") (pin "1") (pinfunction "1_1") (pintype "passive"))
      (node (ref "R21") (pin "2") (pinfunction "2_2") (pintype "passive"))
      (node (ref "R22") (pin "1") (pinfunction "1_1") (pintype "passive"))
    )
    (net (code "57") (name "Net-(R28-Pad1)") (class "Default")
      (node (ref "R28") (pin "1") (pinfunction "1_1") (pintype "passive"))
      (node (ref "R29") (pin "1") (pinfunction "1_1") (pintype "passive"))
      (node (ref "R30") (pin "2") (pinfunction "2_2") (pintype "passive"))
      (node (ref "R31") (pin "1") (pinfunction "1_1") (pintype "passive"))
    )
    (net (code "58") (name "Net-(U1-AIN1)") (class "Default")
      (node (ref "C7") (pin "2") (pinfunction "2_2") (pintype "passive"))
      (node (ref "U1") (pin "B12") (pinfunction "AIN1_B12") (pintype "passive"))
    )
    (net (code "59") (name "Net-(U1-AIP1)") (class "Default")
      (node (ref "C6") (pin "2") (pinfunction "2_2") (pintype "passive"))
      (node (ref "U1") (pin "A12") (pinfunction "AIP1_A12") (pintype "passive"))
    )
    (net (code "60") (name "Net-(U1-ESR_LX)") (class "Default")
      (node (ref "L2") (pin "1") (pinfunction "1_1") (pintype "passive"))
      (node (ref "U1") (pin "K7") (pinfunction "ESR_LX_K7") (pintype "passive"))
    )
    (net (code "61") (name "Net-(U1-OPM_VOUT)") (class "Default")
      (node (ref "C12") (pin "2") (pinfunction "2_2") (pintype "passive"))
      (node (ref "C13") (pin "2") (pinfunction "2_2") (pintype "passive"))
      (node (ref "U1") (pin "K10") (pinfunction "OPM_VOUT_K10") (pintype "passive"))
    )
    (net (code "62") (name "Net-(U1-RAR_LX_VDD11)") (class "Default")
      (node (ref "L1") (pin "1") (pinfunction "1_1") (pintype "passive"))
      (node (ref "U1") (pin "K4") (pinfunction "RAR_LX_VDD11_K4") (pintype "passive"))
    )
    (net (code "63") (name "Net-(U1-TXRTUNE)") (class "Default")
      (node (ref "R45") (pin "2") (pinfunction "2_2") (pintype "passive"))
      (node (ref "U1") (pin "H1") (pinfunction "TXRTUNE_H1") (pintype "passive"))
    )
    (net (code "64") (name "Net-(U1-VSENSE_ESR)") (class "Default")
      (node (ref "C2") (pin "2") (pinfunction "2_2") (pintype "passive"))
      (node (ref "C8") (pin "2") (pinfunction "2_2") (pintype "passive"))
      (node (ref "L2") (pin "2") (pinfunction "2_2") (pintype "passive"))
      (node (ref "R6") (pin "2") (pinfunction "2_2") (pintype "passive"))
      (node (ref "U1") (pin "K8") (pinfunction "VSENSE_ESR_K8") (pintype "passive"))
    )
    (net (code "65") (name "Net-(U1-XTAL_IN)") (class "Default")
      (node (ref "C19") (pin "2") (pinfunction "2_2") (pintype "passive"))
      (node (ref "R9") (pin "2") (pinfunction "2_2") (pintype "passive"))
      (node (ref "U1") (pin "D1") (pinfunction "XTAL_IN_D1") (pintype "passive"))
      (node (ref "Y1") (pin "1") (pinfunction "1_1") (pintype "passive"))
    )
    (net (code "66") (name "Net-(U1-XTAL_OUT)") (class "Default")
      (node (ref "C20") (pin "2") (pinfunction "2_2") (pintype "passive"))
      (node (ref "R9") (pin "1") (pinfunction "1_1") (pintype "passive"))
      (node (ref "U1") (pin "C1") (pinfunction "XTAL_OUT_C1") (pintype "passive"))
      (node (ref "Y1") (pin "3") (pinfunction "3_3") (pintype "passive"))
    )
    (net (code "67") (name "Net-(U5-IN1)") (class "Default")
      (node (ref "R41") (pin "2") (pinfunction "2_2") (pintype "passive"))
      (node (ref "R42") (pin "1") (pinfunction "1_1") (pintype "passive"))
      (node (ref "U5") (pin "4") (pinfunction "IN1_4") (pintype "passive"))
      (node (ref "U5") (pin "8") (pinfunction "IN2_8") (pintype "passive"))
    )
    (net (code "68") (name "Net-(U5-VCC)") (class "Default")
      (node (ref "C39") (pin "2") (pinfunction "2_2") (pintype "passive"))
      (node (ref "D1") (pin "2") (pinfunction "2_2") (pintype "passive"))
      (node (ref "U5") (pin "1") (pinfunction "VCC_1") (pintype "passive"))
    )
    (net (code "69") (name "SNC_PWR") (class "Default")
      (node (ref "C14") (pin "2") (pinfunction "2_2") (pintype "passive"))
      (node (ref "C15") (pin "2") (pinfunction "2_2") (pintype "passive"))
      (node (ref "L3") (pin "2") (pinfunction "2_2") (pintype "passive"))
      (node (ref "P1") (pin "1") (pinfunction "1_1") (pintype "passive"))
      (node (ref "U1") (pin "K5") (pinfunction "AVD_PWR_RAR_K5") (pintype "passive"))
      (node (ref "U1") (pin "K6") (pinfunction "AVD_PWR_ESR_K6") (pintype "passive"))
    )
    (net (code "70") (name "USB_5V") (class "Default")
      (node (ref "D1") (pin "1") (pinfunction "1_1") (pintype "passive"))
      (node (ref "J1") (pin "A4") (pinfunction "VBUS_A4") (pintype "passive"))
      (node (ref "J1") (pin "A9") (pinfunction "VBUS_A9") (pintype "passive"))
      (node (ref "J1") (pin "B4") (pinfunction "VBUS_B4") (pintype "passive"))
      (node (ref "J1") (pin "B9") (pinfunction "VBUS_B9") (pintype "passive"))
    )
    (net (code "71") (name "VBAT") (class "Default")
      (node (ref "C57") (pin "2") (pinfunction "2_2") (pintype "passive"))
      (node (ref "Q3") (pin "3") (pinfunction "S_3") (pintype "passive"))
      (node (ref "R33") (pin "1") (pinfunction "1_1") (pintype "passive"))
    )
    (net (code "72") (name "VDD") (class "Default")
      (node (ref "M1") (pin "2") (pinfunction "L/R_2") (pintype "passive"))
      (node (ref "M3") (pin "2") (pinfunction "L/R_2") (pintype "passive"))
    )
    (net (code "73") (name "VDD_CODEC") (class "Default")
      (node (ref "R6") (pin "1") (pinfunction "1_1") (pintype "passive"))
      (node (ref "TP2") (pin "1") (pinfunction "1_1") (pintype "passive"))
      (node (ref "U1") (pin "K9") (pinfunction "CODEC_VDD_K9") (pintype "passive"))
    )
    (net (code "74") (name "VDD_CORE11") (class "Default")
      (node (ref "C1") (pin "2") (pinfunction "2_2") (pintype "passive"))
      (node (ref "C4") (pin "2") (pinfunction "2_2") (pintype "passive"))
      (node (ref "L1") (pin "2") (pinfunction "2_2") (pintype "passive"))
      (node (ref "TP1") (pin "1") (pinfunction "1_1") (pintype "passive"))
      (node (ref "U1") (pin "K2") (pinfunction "VDD_CORE11_K2") (pintype "passive"))
      (node (ref "U1") (pin "K3") (pinfunction "VSENSE_RAR_K3") (pintype "passive"))
    )
    (net (code "75") (name "VDD_IO33") (class "Default")
      (node (ref "C10") (pin "2") (pinfunction "2_2") (pintype "passive"))
      (node (ref "C9") (pin "2") (pinfunction "2_2") (pintype "passive"))
      (node (ref "TP3") (pin "1") (pinfunction "1_1") (pintype "passive"))
      (node (ref "U1") (pin "K1") (pinfunction "ILR_VOUT_IO33_K1") (pintype "passive"))
    )
    (net (code "76") (name "VDD_IP33") (class "Default")
      (node (ref "C11") (pin "2") (pinfunction "2_2") (pintype "passive"))
      (node (ref "C3") (pin "2") (pinfunction "2_2") (pintype "passive"))
      (node (ref "C53") (pin "2") (pinfunction "2_2") (pintype "passive"))
      (node (ref "C54") (pin "2") (pinfunction "2_2") (pintype "passive"))
      (node (ref "C55") (pin "2") (pinfunction "2_2") (pintype "passive"))
      (node (ref "C56") (pin "2") (pinfunction "2_2") (pintype "passive"))
      (node (ref "M1") (pin "5") (pinfunction "VDD_5") (pintype "power_in"))
      (node (ref "M2") (pin "5") (pinfunction "VDD_5") (pintype "power_in"))
      (node (ref "M3") (pin "5") (pinfunction "VDD_5") (pintype "power_in"))
      (node (ref "M4") (pin "5") (pinfunction "VDD_5") (pintype "power_in"))
      (node (ref "TP4") (pin "1") (pinfunction "1_1") (pintype "passive"))
      (node (ref "U1") (pin "J1") (pinfunction "ILR_VOUT_IP33_J1") (pintype "passive"))
    )
    (net (code "77") (name "V_PWR_IN") (class "Default")
      (node (ref "C58") (pin "2") (pinfunction "2_2") (pintype "passive"))
      (node (ref "C59") (pin "2") (pinfunction "2_2") (pintype "passive"))
      (node (ref "L3") (pin "1") (pinfunction "1_1") (pintype "passive"))
      (node (ref "Q3") (pin "1") (pinfunction "D_1") (pintype "passive"))
    )
    (net (code "78") (name "unconnected-(J1-RX1+-PadB11)") (class "Default")
      (node (ref "J1") (pin "B11") (pinfunction "RX1+_B11") (pintype "passive"))
    )
    (net (code "79") (name "unconnected-(J1-RX1--PadB10)") (class "Default")
      (node (ref "J1") (pin "B10") (pinfunction "RX1-_B10") (pintype "passive"))
    )
    (net (code "80") (name "unconnected-(J1-RX2+-PadA11)") (class "Default")
      (node (ref "J1") (pin "A11") (pinfunction "RX2+_A11") (pintype "passive"))
    )
    (net (code "81") (name "unconnected-(J1-RX2--PadA10)") (class "Default")
      (node (ref "J1") (pin "A10") (pinfunction "RX2-_A10") (pintype "passive"))
    )
    (net (code "82") (name "unconnected-(J1-SBU1-PadA8)") (class "Default")
      (node (ref "J1") (pin "A8") (pinfunction "SBU1_A8") (pintype "passive"))
    )
    (net (code "83") (name "unconnected-(J1-SBU2-PadB8)") (class "Default")
      (node (ref "J1") (pin "B8") (pinfunction "SBU2_B8") (pintype "passive"))
    )
    (net (code "84") (name "unconnected-(J1-TX1+-PadA2)") (class "Default")
      (node (ref "J1") (pin "A2") (pinfunction "TX1+_A2") (pintype "passive"))
    )
    (net (code "85") (name "unconnected-(J1-TX1--PadA3)") (class "Default")
      (node (ref "J1") (pin "A3") (pinfunction "TX1-_A3") (pintype "passive"))
    )
    (net (code "86") (name "unconnected-(J1-TX2+-PadB2)") (class "Default")
      (node (ref "J1") (pin "B2") (pinfunction "TX2+_B2") (pintype "passive"))
    )
    (net (code "87") (name "unconnected-(J1-TX2--PadB3)") (class "Default")
      (node (ref "J1") (pin "B3") (pinfunction "TX2-_B3") (pintype "passive"))
    )
    (net (code "88") (name "unconnected-(U1-AIN2-PadC12)") (class "Default")
      (node (ref "U1") (pin "C12") (pinfunction "AIN2_C12") (pintype "passive"))
    )
    (net (code "89") (name "unconnected-(U1-AIP2-PadD12)") (class "Default")
      (node (ref "U1") (pin "D12") (pinfunction "AIP2_D12") (pintype "passive"))
    )
    (net (code "90") (name "unconnected-(U1-AOHPLN-PadJ12)") (class "Default")
      (node (ref "U1") (pin "J12") (pinfunction "AOHPLN_J12") (pintype "passive"))
    )
    (net (code "91") (name "unconnected-(U1-AOHPLP-PadH12)") (class "Default")
      (node (ref "U1") (pin "H12") (pinfunction "AOHPLP_H12") (pintype "passive"))
    )
    (net (code "92") (name "unconnected-(U1-AOHPRN-PadK12)") (class "Default")
      (node (ref "U1") (pin "K12") (pinfunction "AOHPRN_K12") (pintype "passive"))
    )
    (net (code "93") (name "unconnected-(U1-AOHPRP-PadK11)") (class "Default")
      (node (ref "U1") (pin "K11") (pinfunction "AOHPRP_K11") (pintype "passive"))
    )
    (net (code "94") (name "unconnected-(U1-BACKUP_BOOT-PadB11)") (class "Default")
      (node (ref "U1") (pin "B11") (pinfunction "BACKUP_BOOT_B11") (pintype "passive"))
    )
    (net (code "95") (name "unconnected-(U1-DMIC_CLK11{slash}GPIO8-PadB10)") (class "Default")
      (node (ref "U1") (pin "B10") (pinfunction "DMIC_CLK11/GPIO8_B10") (pintype "passive"))
    )
    (net (code "96") (name "unconnected-(U1-DMIC_IN1{slash}GPIO9-PadA10)") (class "Default")
      (node (ref "U1") (pin "A10") (pinfunction "DMIC_IN1/GPIO9_A10") (pintype "passive"))
    )
    (net (code "97") (name "unconnected-(U1-GPIOAO_DATA0{slash}ALWAYS_ON-PadJ8)") (class "Default")
      (node (ref "U1") (pin "J8") (pinfunction "GPIOAO_DATA0/ALWAYS_ON_J8") (pintype "passive"))
    )
    (net (code "98") (name "unconnected-(U1-GPIO_DAT0{slash}I2S1_CLK-PadB4)") (class "Default")
      (node (ref "U1") (pin "B4") (pinfunction "GPIO_DAT0/I2S1_CLK_B4") (pintype "passive"))
    )
    (net (code "99") (name "unconnected-(U1-GPIO_DAT1{slash}I2S1_WS-PadB5)") (class "Default")
      (node (ref "U1") (pin "B5") (pinfunction "GPIO_DAT1/I2S1_WS_B5") (pintype "passive"))
    )
    (net (code "100") (name "unconnected-(U1-GPIO_DAT2{slash}I2S1_SDI-PadB6)") (class "Default")
      (node (ref "U1") (pin "B6") (pinfunction "GPIO_DAT2/I2S1_SDI_B6") (pintype "passive"))
    )
    (net (code "101") (name "unconnected-(U1-GPIO_DAT3{slash}I2S1_SDO-PadB7)") (class "Default")
      (node (ref "U1") (pin "B7") (pinfunction "GPIO_DAT3/I2S1_SDO_B7") (pintype "passive"))
    )
    (net (code "102") (name "unconnected-(U1-GPIO_DAT10{slash}2C2_CLK-PadJ4)") (class "Default")
      (node (ref "U1") (pin "J4") (pinfunction "GPIO_DAT10/2C2_CLK_J4") (pintype "passive"))
    )
    (net (code "103") (name "unconnected-(U1-GPIO_DAT11{slash}I2C2_DAT-PadJ3)") (class "Default")
      (node (ref "U1") (pin "J3") (pinfunction "GPIO_DAT11/I2C2_DAT_J3") (pintype "passive"))
    )
    (net (code "104") (name "unconnected-(U1-I2C_CLK-PadA3)") (class "Default")
      (node (ref "U1") (pin "A3") (pinfunction "I2C_CLK_A3") (pintype "passive"))
    )
    (net (code "105") (name "unconnected-(U1-I2C_DAT-PadB3)") (class "Default")
      (node (ref "U1") (pin "B3") (pinfunction "I2C_DAT_B3") (pintype "passive"))
    )
    (net (code "106") (name "unconnected-(U1-MICBIAS2-PadE12)") (class "Default")
      (node (ref "U1") (pin "E12") (pinfunction "MICBIAS2_E12") (pintype "passive"))
    )
    (net (code "107") (name "unconnected-(U1-NC-PadJ7)") (class "Default")
      (node (ref "U1") (pin "J7") (pinfunction "NC_J7") (pintype "passive"))
    )
    (net (code "108") (name "unconnected-(U1-VBUS-PadE1)") (class "Default")
      (node (ref "U1") (pin "E1") (pinfunction "VBUS_E1") (pintype "passive"))
    )
    (net (code "109") (name "unconnected-(U1-VINP0_ADC-PadB1)") (class "Default")
      (node (ref "U1") (pin "B1") (pinfunction "VINP0_ADC_B1") (pintype "passive"))
    )
    (net (code "110") (name "unconnected-(U1-VINP1_ADC-PadB2)") (class "Default")
      (node (ref "U1") (pin "B2") (pinfunction "VINP1_ADC_B2") (pintype "passive"))
    )
  )
)
